# 2022.net
KiCad netlist of a schematic drawn in EasyEDA Pro
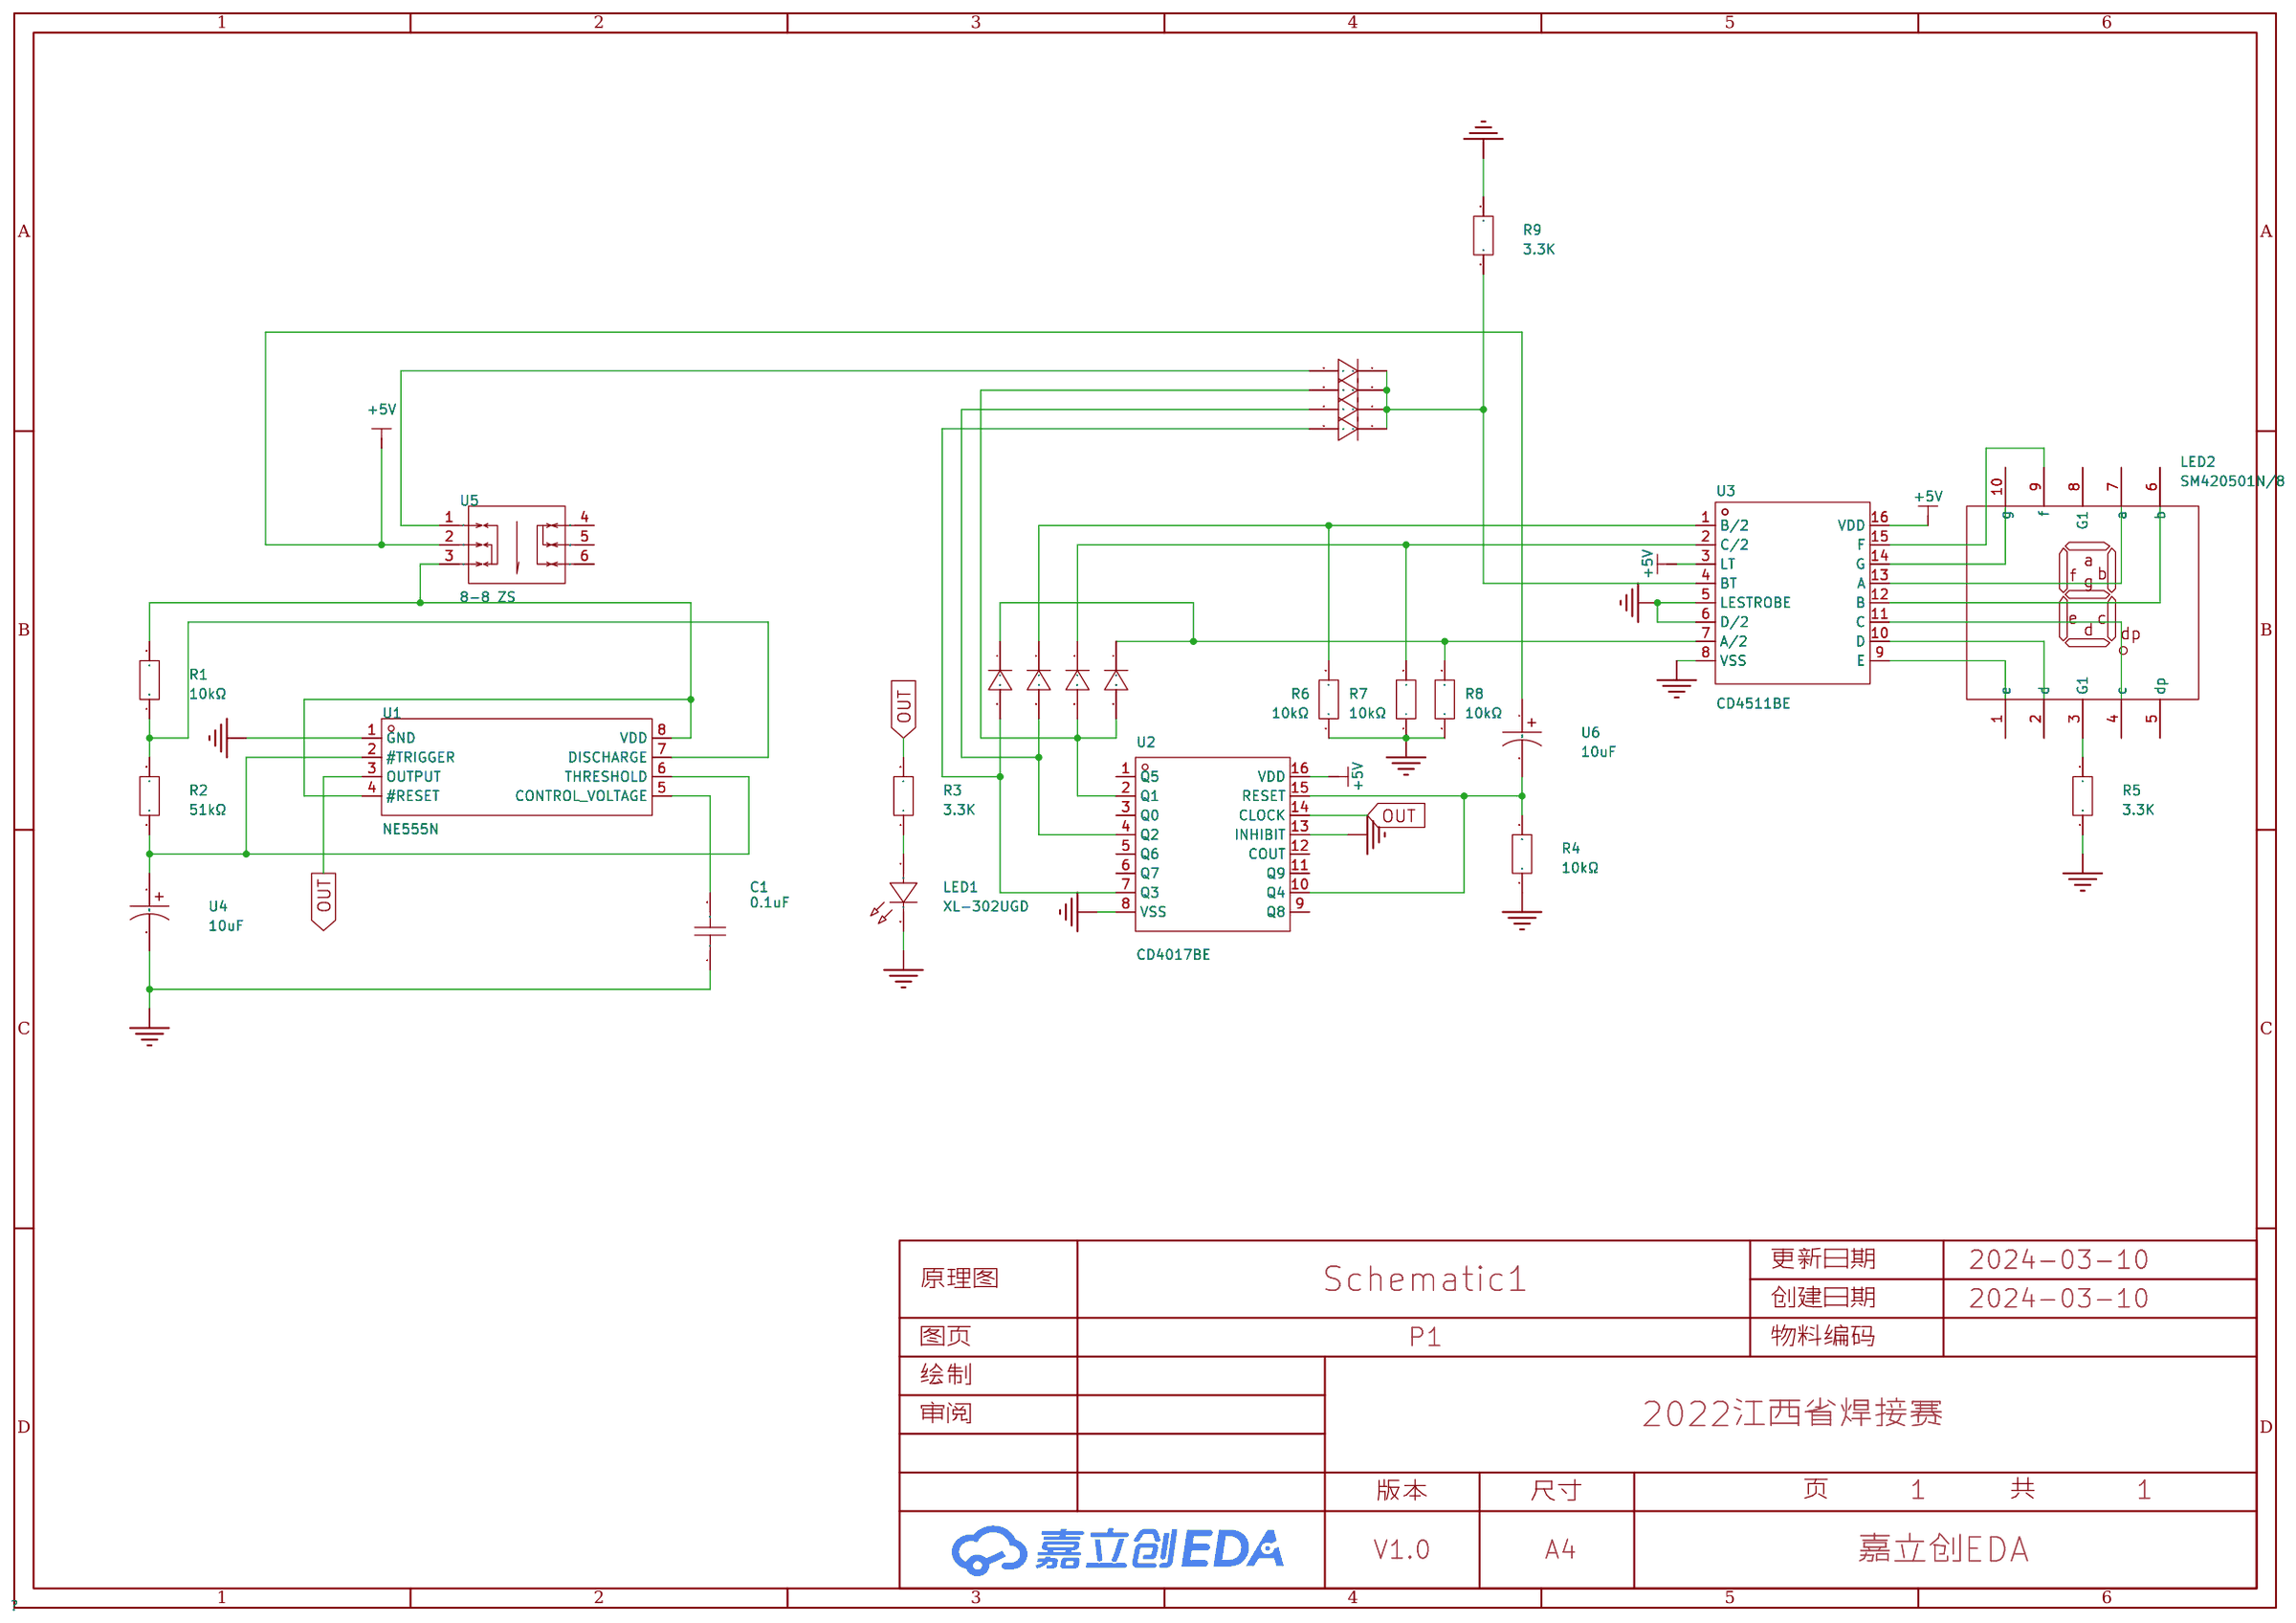
[diagram p0: schematic sheet]

(export (version "E")
  (design (tool "Eeschema 10.0.6"))
  (components
    (comp (ref "C1")
      (value "0.1uF")
      (footprint "easyedapro:CAP-TH_L5.0-W2.5-P5.08-D0.7")
      (description "容值:100nF;精度:-20%~+80%;额定电压:50V;温度系数:Y5V;")
      (fields
        (field (name "Manufacturer Part") "CC1H104ZC74D3F5O30MN")
        (field (name "Manufacturer") "Dersonic(德尔创)")
      )
      (libsource (lib "easyedapro") (part "CC1H104ZC74D3F5O30MN"))
    )
    (comp (ref "D1")
      (value "1N4148")
      (footprint "easyedapro:DO-35_BD2.0-L4.0-P8.0-D0.5-RD")
      (description "二极管配置:-;正向压降(Vf):-;直流反向耐压(Vr):-;平均整流电流(Io):-;")
      (libsource (lib "easyedapro") (part "1N4148_C13769"))
    )
    (comp (ref "D2")
      (value "1N4148")
      (footprint "easyedapro:DO-35_BD2.0-L4.0-P8.0-D0.5-RD")
      (description "二极管配置:-;正向压降(Vf):-;直流反向耐压(Vr):-;平均整流电流(Io):-;")
      (libsource (lib "easyedapro") (part "1N4148_C13769"))
    )
    (comp (ref "D3")
      (value "1N4148")
      (footprint "easyedapro:DO-35_BD2.0-L4.0-P8.0-D0.5-RD")
      (description "二极管配置:-;正向压降(Vf):-;直流反向耐压(Vr):-;平均整流电流(Io):-;")
      (libsource (lib "easyedapro") (part "1N4148_C13769"))
    )
    (comp (ref "D4")
      (value "1N4148")
      (footprint "easyedapro:DO-35_BD2.0-L4.0-P8.0-D0.5-RD")
      (description "二极管配置:-;正向压降(Vf):-;直流反向耐压(Vr):-;平均整流电流(Io):-;")
      (libsource (lib "easyedapro") (part "1N4148_C13769"))
    )
    (comp (ref "D5")
      (value "1N4148")
      (footprint "easyedapro:DO-35_BD2.0-L4.0-P8.0-D0.5-RD")
      (description "二极管配置:-;正向压降(Vf):-;直流反向耐压(Vr):-;平均整流电流(Io):-;")
      (libsource (lib "easyedapro") (part "1N4148_C13769"))
    )
    (comp (ref "D6")
      (value "1N4148")
      (footprint "easyedapro:DO-35_BD2.0-L4.0-P8.0-D0.5-RD")
      (description "二极管配置:-;正向压降(Vf):-;直流反向耐压(Vr):-;平均整流电流(Io):-;")
      (libsource (lib "easyedapro") (part "1N4148_C13769"))
    )
    (comp (ref "D7")
      (value "1N4148")
      (footprint "easyedapro:DO-35_BD2.0-L4.0-P8.0-D0.5-RD")
      (description "二极管配置:-;正向压降(Vf):-;直流反向耐压(Vr):-;平均整流电流(Io):-;")
      (libsource (lib "easyedapro") (part "1N4148_C13769"))
    )
    (comp (ref "D8")
      (value "1N4148")
      (footprint "easyedapro:DO-35_BD2.0-L4.0-P8.0-D0.5-RD")
      (description "二极管配置:-;正向压降(Vf):-;直流反向耐压(Vr):-;平均整流电流(Io):-;")
      (libsource (lib "easyedapro") (part "1N4148_C13769"))
    )
    (comp (ref "LED1")
      (value "XL-302UGD")
      (footprint "easyedapro:LED-TH_BD3.8-P2.54-FD_GREEN")
      (fields (field (name "Manufacturer") "XINGLIGHT(成兴光)"))
      (libsource (lib "easyedapro") (part "XL-302UGD"))
    )
    (comp (ref "LED2")
      (value "SM420501N/8")
      (footprint "easyedapro:LED-SEG-TH_10P-L12.7-W19.0-P2.54-S15.24-BL")
      (description "数码管位数:1位;发光颜色:红色;LED极性:共阴极;数字/字母大小(英寸):0.5;")
      (fields (field (name "Manufacturer") "ARKLED(方舟)"))
      (libsource (lib "easyedapro") (part "SM420501N/8"))
    )
    (comp (ref "R1")
      (value "10kΩ")
      (footprint "easyedapro:RES-TH_BD2.3-L6.5-P10.50-D0.5")
      (description "电阻类型:金属膜电阻;阻值:1kΩ;精度:±1%;功率:250mW;温度系数:±200ppm/°C;")
      (fields (field (name "Manufacturer Part") "MF1/4W-1KΩ±1%T52") (field (name "Manufacturer") "华星机电"))
      (libsource (lib "easyedapro") (part "MF1/4W-1KΩ±1%T52"))
    )
    (comp (ref "R2")
      (value "51kΩ")
      (footprint "easyedapro:RES-TH_BD2.3-L6.5-P10.50-D0.5")
      (description "电阻类型:金属膜电阻;阻值:1kΩ;精度:±1%;功率:250mW;温度系数:±200ppm/°C;")
      (fields (field (name "Manufacturer Part") "MF1/4W-1KΩ±1%T52") (field (name "Manufacturer") "华星机电"))
      (libsource (lib "easyedapro") (part "MF1/4W-1KΩ±1%T52"))
    )
    (comp (ref "R3")
      (value "3.3K")
      (footprint "easyedapro:RES-TH_BD2.3-L6.5-P10.50-D0.5")
      (description "电阻类型:金属膜电阻;阻值:1kΩ;精度:±1%;功率:250mW;温度系数:±200ppm/°C;")
      (fields (field (name "Manufacturer Part") "MF1/4W-1KΩ±1%T52") (field (name "Manufacturer") "华星机电"))
      (libsource (lib "easyedapro") (part "MF1/4W-1KΩ±1%T52"))
    )
    (comp (ref "R4")
      (value "10kΩ")
      (footprint "easyedapro:RES-TH_BD2.3-L6.5-P10.50-D0.5")
      (description "电阻类型:金属膜电阻;阻值:1kΩ;精度:±1%;功率:250mW;温度系数:±200ppm/°C;")
      (fields (field (name "Manufacturer Part") "MF1/4W-1KΩ±1%T52") (field (name "Manufacturer") "华星机电"))
      (libsource (lib "easyedapro") (part "MF1/4W-1KΩ±1%T52"))
    )
    (comp (ref "R5")
      (value "3.3K")
      (footprint "easyedapro:RES-TH_BD2.3-L6.5-P10.50-D0.5")
      (description "电阻类型:金属膜电阻;阻值:1kΩ;精度:±1%;功率:250mW;温度系数:±200ppm/°C;")
      (fields (field (name "Manufacturer Part") "MF1/4W-1KΩ±1%T52") (field (name "Manufacturer") "华星机电"))
      (libsource (lib "easyedapro") (part "MF1/4W-1KΩ±1%T52"))
    )
    (comp (ref "R6")
      (value "10kΩ")
      (footprint "easyedapro:RES-TH_BD2.3-L6.5-P10.50-D0.5")
      (description "电阻类型:金属膜电阻;阻值:1kΩ;精度:±1%;功率:250mW;温度系数:±200ppm/°C;")
      (fields (field (name "Manufacturer Part") "MF1/4W-1KΩ±1%T52") (field (name "Manufacturer") "华星机电"))
      (libsource (lib "easyedapro") (part "MF1/4W-1KΩ±1%T52"))
    )
    (comp (ref "R7")
      (value "10kΩ")
      (footprint "easyedapro:RES-TH_BD2.3-L6.5-P10.50-D0.5")
      (description "电阻类型:金属膜电阻;阻值:1kΩ;精度:±1%;功率:250mW;温度系数:±200ppm/°C;")
      (fields (field (name "Manufacturer Part") "MF1/4W-1KΩ±1%T52") (field (name "Manufacturer") "华星机电"))
      (libsource (lib "easyedapro") (part "MF1/4W-1KΩ±1%T52"))
    )
    (comp (ref "R8")
      (value "10kΩ")
      (footprint "easyedapro:RES-TH_BD2.3-L6.5-P10.50-D0.5")
      (description "电阻类型:金属膜电阻;阻值:1kΩ;精度:±1%;功率:250mW;温度系数:±200ppm/°C;")
      (fields (field (name "Manufacturer Part") "MF1/4W-1KΩ±1%T52") (field (name "Manufacturer") "华星机电"))
      (libsource (lib "easyedapro") (part "MF1/4W-1KΩ±1%T52"))
    )
    (comp (ref "R9")
      (value "3.3K")
      (footprint "easyedapro:RES-TH_BD2.3-L6.5-P10.50-D0.5")
      (description "电阻类型:金属膜电阻;阻值:1kΩ;精度:±1%;功率:250mW;温度系数:±200ppm/°C;")
      (fields (field (name "Manufacturer Part") "MF1/4W-1KΩ±1%T52") (field (name "Manufacturer") "华星机电"))
      (libsource (lib "easyedapro") (part "MF1/4W-1KΩ±1%T52"))
    )
    (comp (ref "U1")
      (value "NE555N")
      (footprint "easyedapro:DIP-8_L9.7-W6.4-P2.54-LS7.6-BL")
      (fields (field (name "Manufacturer") "HTC"))
      (libsource (lib "easyedapro") (part "NE555N_C510566"))
    )
    (comp (ref "U2")
      (value "CD4017BE")
      (footprint "easyedapro:DIP-16_L19.2-W6.6-P2.54-LS7.6-BL")
      (fields (field (name "Manufacturer") "HGSEMI(华冠)"))
      (libsource (lib "easyedapro") (part "CD4017BE_C507168"))
    )
    (comp (ref "U3")
      (value "CD4511BE")
      (footprint "easyedapro:DIP-16_L19.8-W6.5-P2.54-LS7.6-BL")
      (description "CD4511B CMOS BCD 到 7 段 LED 锁存解码器驱动器")
      (fields (field (name "Manufacturer") "TI(德州仪器)"))
      (libsource (lib "easyedapro") (part "CD4511BE"))
    )
    (comp (ref "U4")
      (value "10uF")
      (footprint "easyedapro:CAP-TH_BD6.3-P2.50-D0.5-FD")
      (description "容值:10uF;精度:±20%;额定电压:400V;纹波电流:-;等效串联电阻:-;")
      (fields
        (field (name "Manufacturer Part") "MHT10UF400V87EC0217")
        (field (name "Manufacturer") "KNSCHA(科尼盛)")
      )
      (libsource (lib "easyedapro") (part "MHT10UF400V87EC0217"))
    )
    (comp (ref "U5")
      (value "8-8 ZS")
      (footprint "easyedapro:SW-TH_6P-L8.0-W8.0-P2.50")
      (description "电路结构:双刀双掷;自锁/无锁:自锁;安装方式:直插;触点电流:100mA;额定电压 (AC):-;额定电压 (DC):30V;带灯:不带;作用力:180gf;机械寿命:5千次;")
      (fields (field (name "Manufacturer") "SHOU HAN(首韩)"))
      (libsource (lib "easyedapro") (part "8-8 ZS"))
    )
    (comp (ref "U6")
      (value "10uF")
      (footprint "easyedapro:CAP-TH_BD6.3-P2.50-D0.5-FD")
      (description "容值:10uF;精度:±20%;额定电压:400V;纹波电流:-;等效串联电阻:-;")
      (fields
        (field (name "Manufacturer Part") "MHT10UF400V87EC0217")
        (field (name "Manufacturer") "KNSCHA(科尼盛)")
      )
      (libsource (lib "easyedapro") (part "MHT10UF400V87EC0217"))
    )
  )
  (nets
    (net (code "1") (name "+5V") (class "Default")
      (node (ref "U2") (pin "16") (pinfunction "VDD_16") (pintype "unspecified"))
      (node (ref "U3") (pin "16") (pinfunction "VDD_16") (pintype "input"))
      (node (ref "U3") (pin "3") (pinfunction "LT_3") (pintype "input"))
      (node (ref "U5") (pin "2") (pinfunction "2_2") (pintype "unspecified"))
      (node (ref "U6") (pin "1") (pinfunction "1_1") (pintype "unspecified"))
    )
    (net (code "2") (name "GND") (class "Default")
      (node (ref "C1") (pin "1") (pinfunction "1_1") (pintype "unspecified"))
      (node (ref "LED1") (pin "2") (pinfunction "K_2") (pintype "unspecified"))
      (node (ref "R4") (pin "1") (pinfunction "1_1") (pintype "unspecified"))
      (node (ref "R5") (pin "1") (pinfunction "1_1") (pintype "unspecified"))
      (node (ref "R6") (pin "1") (pinfunction "1_1") (pintype "unspecified"))
      (node (ref "R7") (pin "1") (pinfunction "1_1") (pintype "unspecified"))
      (node (ref "R8") (pin "1") (pinfunction "1_1") (pintype "unspecified"))
      (node (ref "R9") (pin "2") (pinfunction "2_2") (pintype "unspecified"))
      (node (ref "U1") (pin "1") (pinfunction "GND_1") (pintype "input"))
      (node (ref "U2") (pin "13") (pinfunction "INHIBIT_13") (pintype "unspecified"))
      (node (ref "U2") (pin "8") (pinfunction "VSS_8") (pintype "unspecified"))
      (node (ref "U3") (pin "5") (pinfunction "LESTROBE_5") (pintype "input"))
      (node (ref "U3") (pin "6") (pinfunction "D/2_6") (pintype "input"))
      (node (ref "U3") (pin "8") (pinfunction "VSS_8") (pintype "input"))
      (node (ref "U4") (pin "2") (pinfunction "2_2") (pintype "unspecified"))
    )
    (net (code "3") (name "Net-(D1-Pad2)") (class "Default")
      (node (ref "D1") (pin "2") (pinfunction "2_2") (pintype "unspecified"))
      (node (ref "U5") (pin "1") (pinfunction "1_1") (pintype "unspecified"))
    )
    (net (code "4") (name "Net-(LED1-A)") (class "Default")
      (node (ref "LED1") (pin "1") (pinfunction "A_1") (pintype "unspecified"))
      (node (ref "R3") (pin "1") (pinfunction "1_1") (pintype "unspecified"))
    )
    (net (code "5") (name "Net-(LED2-G1-Pad3)") (class "Default")
      (node (ref "LED2") (pin "3") (pinfunction "G1_3") (pintype "input"))
      (node (ref "R5") (pin "2") (pinfunction "2_2") (pintype "unspecified"))
    )
    (net (code "6") (name "Net-(LED2-a)") (class "Default")
      (node (ref "LED2") (pin "7") (pinfunction "a_7") (pintype "input"))
      (node (ref "U3") (pin "13") (pinfunction "A_13") (pintype "input"))
    )
    (net (code "7") (name "Net-(LED2-b)") (class "Default")
      (node (ref "LED2") (pin "6") (pinfunction "b_6") (pintype "input"))
      (node (ref "U3") (pin "12") (pinfunction "B_12") (pintype "input"))
    )
    (net (code "8") (name "Net-(LED2-c)") (class "Default")
      (node (ref "LED2") (pin "4") (pinfunction "c_4") (pintype "input"))
      (node (ref "U3") (pin "11") (pinfunction "C_11") (pintype "input"))
    )
    (net (code "9") (name "Net-(LED2-d)") (class "Default")
      (node (ref "LED2") (pin "2") (pinfunction "d_2") (pintype "input"))
      (node (ref "U3") (pin "10") (pinfunction "D_10") (pintype "input"))
    )
    (net (code "10") (name "Net-(LED2-e)") (class "Default")
      (node (ref "LED2") (pin "1") (pinfunction "e_1") (pintype "input"))
      (node (ref "U3") (pin "9") (pinfunction "E_9") (pintype "input"))
    )
    (net (code "11") (name "Net-(LED2-f)") (class "Default")
      (node (ref "LED2") (pin "9") (pinfunction "f_9") (pintype "input"))
      (node (ref "U3") (pin "15") (pinfunction "F_15") (pintype "input"))
    )
    (net (code "12") (name "Net-(LED2-g)") (class "Default")
      (node (ref "LED2") (pin "10") (pinfunction "g_10") (pintype "input"))
      (node (ref "U3") (pin "14") (pinfunction "G_14") (pintype "input"))
    )
    (net (code "13") (name "Net-(U1-#RESET)") (class "Default")
      (node (ref "R1") (pin "2") (pinfunction "2_2") (pintype "unspecified"))
      (node (ref "U1") (pin "4") (pinfunction "#RESET_4") (pintype "input"))
      (node (ref "U1") (pin "8") (pinfunction "VDD_8") (pintype "input"))
      (node (ref "U5") (pin "3") (pinfunction "3_3") (pintype "unspecified"))
    )
    (net (code "14") (name "Net-(U1-#TRIGGER)") (class "Default")
      (node (ref "R2") (pin "1") (pinfunction "1_1") (pintype "unspecified"))
      (node (ref "U1") (pin "2") (pinfunction "#TRIGGER_2") (pintype "input"))
      (node (ref "U1") (pin "6") (pinfunction "THRESHOLD_6") (pintype "input"))
      (node (ref "U4") (pin "1") (pinfunction "1_1") (pintype "unspecified"))
    )
    (net (code "15") (name "Net-(U1-CONTROL_VOLTAGE)") (class "Default")
      (node (ref "C1") (pin "2") (pinfunction "2_2") (pintype "unspecified"))
      (node (ref "U1") (pin "5") (pinfunction "CONTROL_VOLTAGE_5") (pintype "input"))
    )
    (net (code "16") (name "Net-(U1-DISCHARGE)") (class "Default")
      (node (ref "R1") (pin "1") (pinfunction "1_1") (pintype "unspecified"))
      (node (ref "R2") (pin "2") (pinfunction "2_2") (pintype "unspecified"))
      (node (ref "U1") (pin "7") (pinfunction "DISCHARGE_7") (pintype "input"))
    )
    (net (code "17") (name "Net-(U2-Q1)") (class "Default")
      (node (ref "D2") (pin "2") (pinfunction "2_2") (pintype "unspecified"))
      (node (ref "D3") (pin "2") (pinfunction "2_2") (pintype "unspecified"))
      (node (ref "D6") (pin "2") (pinfunction "2_2") (pintype "unspecified"))
      (node (ref "U2") (pin "2") (pinfunction "Q1_2") (pintype "unspecified"))
    )
    (net (code "18") (name "Net-(U2-Q2)") (class "Default")
      (node (ref "D4") (pin "2") (pinfunction "2_2") (pintype "unspecified"))
      (node (ref "D7") (pin "2") (pinfunction "2_2") (pintype "unspecified"))
      (node (ref "U2") (pin "4") (pinfunction "Q2_4") (pintype "unspecified"))
    )
    (net (code "19") (name "Net-(U2-Q3)") (class "Default")
      (node (ref "D5") (pin "2") (pinfunction "2_2") (pintype "unspecified"))
      (node (ref "D8") (pin "2") (pinfunction "2_2") (pintype "unspecified"))
      (node (ref "U2") (pin "7") (pinfunction "Q3_7") (pintype "unspecified"))
    )
    (net (code "20") (name "Net-(U2-Q4)") (class "Default")
      (node (ref "R4") (pin "2") (pinfunction "2_2") (pintype "unspecified"))
      (node (ref "U2") (pin "10") (pinfunction "Q4_10") (pintype "unspecified"))
      (node (ref "U2") (pin "15") (pinfunction "RESET_15") (pintype "unspecified"))
      (node (ref "U6") (pin "2") (pinfunction "2_2") (pintype "unspecified"))
    )
    (net (code "21") (name "Net-(U3-A{slash}2)") (class "Default")
      (node (ref "D3") (pin "1") (pinfunction "1_1") (pintype "unspecified"))
      (node (ref "D5") (pin "1") (pinfunction "1_1") (pintype "unspecified"))
      (node (ref "R8") (pin "2") (pinfunction "2_2") (pintype "unspecified"))
      (node (ref "U3") (pin "7") (pinfunction "A/2_7") (pintype "input"))
    )
    (net (code "22") (name "Net-(U3-BT)") (class "Default")
      (node (ref "D1") (pin "1") (pinfunction "1_1") (pintype "unspecified"))
      (node (ref "D6") (pin "1") (pinfunction "1_1") (pintype "unspecified"))
      (node (ref "D7") (pin "1") (pinfunction "1_1") (pintype "unspecified"))
      (node (ref "D8") (pin "1") (pinfunction "1_1") (pintype "unspecified"))
      (node (ref "R9") (pin "1") (pinfunction "1_1") (pintype "unspecified"))
      (node (ref "U3") (pin "4") (pinfunction "BT_4") (pintype "input"))
    )
    (net (code "23") (name "Net-(U3-B{slash}2)") (class "Default")
      (node (ref "D4") (pin "1") (pinfunction "1_1") (pintype "unspecified"))
      (node (ref "R6") (pin "2") (pinfunction "2_2") (pintype "unspecified"))
      (node (ref "U3") (pin "1") (pinfunction "B/2_1") (pintype "input"))
    )
    (net (code "24") (name "Net-(U3-C{slash}2)") (class "Default")
      (node (ref "D2") (pin "1") (pinfunction "1_1") (pintype "unspecified"))
      (node (ref "R7") (pin "2") (pinfunction "2_2") (pintype "unspecified"))
      (node (ref "U3") (pin "2") (pinfunction "C/2_2") (pintype "input"))
    )
    (net (code "25") (name "OUT") (class "Default")
      (node (ref "R3") (pin "2") (pinfunction "2_2") (pintype "unspecified"))
      (node (ref "U1") (pin "3") (pinfunction "OUTPUT_3") (pintype "input"))
      (node (ref "U2") (pin "14") (pinfunction "CLOCK_14") (pintype "unspecified"))
    )
    (net (code "26") (name "unconnected-(LED2-G1-Pad8)") (class "Default")
      (node (ref "LED2") (pin "8") (pinfunction "G1_8") (pintype "input"))
    )
    (net (code "27") (name "unconnected-(LED2-dp-Pad5)") (class "Default")
      (node (ref "LED2") (pin "5") (pinfunction "dp_5") (pintype "input"))
    )
    (net (code "28") (name "unconnected-(U2-COUT-Pad12)") (class "Default")
      (node (ref "U2") (pin "12") (pinfunction "COUT_12") (pintype "unspecified"))
    )
    (net (code "29") (name "unconnected-(U2-Q0-Pad3)") (class "Default")
      (node (ref "U2") (pin "3") (pinfunction "Q0_3") (pintype "unspecified"))
    )
    (net (code "30") (name "unconnected-(U2-Q5-Pad1)") (class "Default")
      (node (ref "U2") (pin "1") (pinfunction "Q5_1") (pintype "unspecified"))
    )
    (net (code "31") (name "unconnected-(U2-Q6-Pad5)") (class "Default")
      (node (ref "U2") (pin "5") (pinfunction "Q6_5") (pintype "unspecified"))
    )
    (net (code "32") (name "unconnected-(U2-Q7-Pad6)") (class "Default")
      (node (ref "U2") (pin "6") (pinfunction "Q7_6") (pintype "unspecified"))
    )
    (net (code "33") (name "unconnected-(U2-Q8-Pad9)") (class "Default")
      (node (ref "U2") (pin "9") (pinfunction "Q8_9") (pintype "unspecified"))
    )
    (net (code "34") (name "unconnected-(U2-Q9-Pad11)") (class "Default")
      (node (ref "U2") (pin "11") (pinfunction "Q9_11") (pintype "unspecified"))
    )
    (net (code "35") (name "unconnected-(U5-Pad4)") (class "Default")
      (node (ref "U5") (pin "4") (pinfunction "4_4") (pintype "unspecified"))
    )
    (net (code "36") (name "unconnected-(U5-Pad5)") (class "Default")
      (node (ref "U5") (pin "5") (pinfunction "5_5") (pintype "unspecified"))
    )
    (net (code "37") (name "unconnected-(U5-Pad6)") (class "Default")
      (node (ref "U5") (pin "6") (pinfunction "6_6") (pintype "unspecified"))
    )
  )
)
